# TailLightPrototypeRev3LEDs.net
KiCad netlist of a schematic drawn in Altium Designer
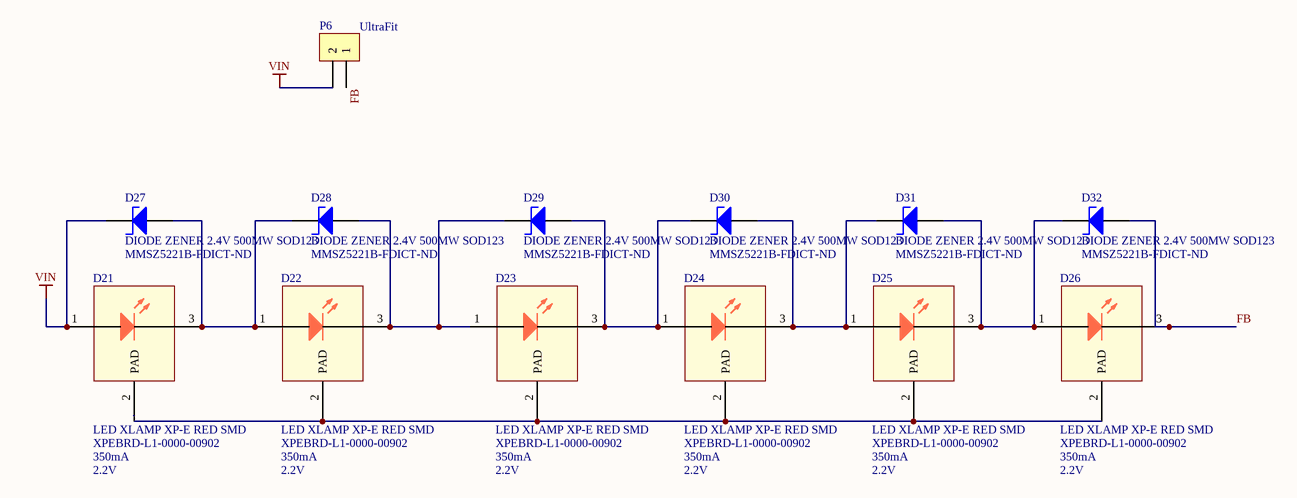
[diagram p0: TailLightPrototypeRev3LEDs.SchDoc]

(export (version "E")
  (design (tool "Eeschema 10.0.6"))
  (components
    (comp (ref "D21")
      (value "LED XLAMP XP-E RED SMD")
      (footprint "LED CREE XP-E2 1414 2-SMD")
      (description "LED Lighting Color XLamp® XP-E2 Red 623nm (620nm ~ 625nm) 1414 (3535 Metric)")
      (fields
        (field (name "MANUFACTURER") "Cree")
        (field (name "MANUFACTURER PART NUMBER") "XPEBRD-L1-0000-00902")
        (field (name "TEST CURRENT") "350mA")
        (field (name "FORWARD VOLTAGE") "2.2V")
      )
      (libsource (lib "Schematic Diagrams") (part "LED XLAMP XP-E RED SMD"))
    )
    (comp (ref "D22")
      (value "LED XLAMP XP-E RED SMD")
      (footprint "LED CREE XP-E2 1414 2-SMD")
      (description "LED Lighting Color XLamp® XP-E2 Red 623nm (620nm ~ 625nm) 1414 (3535 Metric)")
      (fields
        (field (name "MANUFACTURER") "Cree")
        (field (name "MANUFACTURER PART NUMBER") "XPEBRD-L1-0000-00902")
        (field (name "TEST CURRENT") "350mA")
        (field (name "FORWARD VOLTAGE") "2.2V")
      )
      (libsource (lib "Schematic Diagrams") (part "LED XLAMP XP-E RED SMD"))
    )
    (comp (ref "D23")
      (value "LED XLAMP XP-E RED SMD")
      (footprint "LED CREE XP-E2 1414 2-SMD")
      (description "LED Lighting Color XLamp® XP-E2 Red 623nm (620nm ~ 625nm) 1414 (3535 Metric)")
      (fields
        (field (name "MANUFACTURER") "Cree")
        (field (name "MANUFACTURER PART NUMBER") "XPEBRD-L1-0000-00902")
        (field (name "TEST CURRENT") "350mA")
        (field (name "FORWARD VOLTAGE") "2.2V")
      )
      (libsource (lib "Schematic Diagrams") (part "LED XLAMP XP-E RED SMD"))
    )
    (comp (ref "D24")
      (value "LED XLAMP XP-E RED SMD")
      (footprint "LED CREE XP-E2 1414 2-SMD")
      (description "LED Lighting Color XLamp® XP-E2 Red 623nm (620nm ~ 625nm) 1414 (3535 Metric)")
      (fields
        (field (name "MANUFACTURER") "Cree")
        (field (name "MANUFACTURER PART NUMBER") "XPEBRD-L1-0000-00902")
        (field (name "TEST CURRENT") "350mA")
        (field (name "FORWARD VOLTAGE") "2.2V")
      )
      (libsource (lib "Schematic Diagrams") (part "LED XLAMP XP-E RED SMD"))
    )
    (comp (ref "D25")
      (value "LED XLAMP XP-E RED SMD")
      (footprint "LED CREE XP-E2 1414 2-SMD")
      (description "LED Lighting Color XLamp® XP-E2 Red 623nm (620nm ~ 625nm) 1414 (3535 Metric)")
      (fields
        (field (name "MANUFACTURER") "Cree")
        (field (name "MANUFACTURER PART NUMBER") "XPEBRD-L1-0000-00902")
        (field (name "TEST CURRENT") "350mA")
        (field (name "FORWARD VOLTAGE") "2.2V")
      )
      (libsource (lib "Schematic Diagrams") (part "LED XLAMP XP-E RED SMD"))
    )
    (comp (ref "D26")
      (value "LED XLAMP XP-E RED SMD")
      (footprint "LED CREE XP-E2 1414 2-SMD")
      (description "LED Lighting Color XLamp® XP-E2 Red 623nm (620nm ~ 625nm) 1414 (3535 Metric)")
      (fields
        (field (name "MANUFACTURER") "Cree")
        (field (name "MANUFACTURER PART NUMBER") "XPEBRD-L1-0000-00902")
        (field (name "TEST CURRENT") "350mA")
        (field (name "FORWARD VOLTAGE") "2.2V")
      )
      (libsource (lib "Schematic Diagrams") (part "LED XLAMP XP-E RED SMD"))
    )
    (comp (ref "D27")
      (value "DIODE ZENER 2.4V 500MW SOD123")
      (footprint "DIODE SOD123")
      (description "Zener Diode 2.4V 500mW ±5% Surface Mount SOD-123")
      (fields (field (name "TOLERANCE") "5%") (field (name "SUPPLIER PART NUMBER 1") "MMSZ5221B-FDICT-ND"))
      (libsource (lib "Schematic Diagrams") (part "DIODE ZENER 2.4V 500MW SOD123"))
    )
    (comp (ref "D28")
      (value "DIODE ZENER 2.4V 500MW SOD123")
      (footprint "DIODE SOD123")
      (description "Zener Diode 2.4V 500mW ±5% Surface Mount SOD-123")
      (fields (field (name "TOLERANCE") "5%") (field (name "SUPPLIER PART NUMBER 1") "MMSZ5221B-FDICT-ND"))
      (libsource (lib "Schematic Diagrams") (part "DIODE ZENER 2.4V 500MW SOD123"))
    )
    (comp (ref "D29")
      (value "DIODE ZENER 2.4V 500MW SOD123")
      (footprint "DIODE SOD123")
      (description "Zener Diode 2.4V 500mW ±5% Surface Mount SOD-123")
      (fields (field (name "TOLERANCE") "5%") (field (name "SUPPLIER PART NUMBER 1") "MMSZ5221B-FDICT-ND"))
      (libsource (lib "Schematic Diagrams") (part "DIODE ZENER 2.4V 500MW SOD123"))
    )
    (comp (ref "D30")
      (value "DIODE ZENER 2.4V 500MW SOD123")
      (footprint "DIODE SOD123")
      (description "Zener Diode 2.4V 500mW ±5% Surface Mount SOD-123")
      (fields (field (name "TOLERANCE") "5%") (field (name "SUPPLIER PART NUMBER 1") "MMSZ5221B-FDICT-ND"))
      (libsource (lib "Schematic Diagrams") (part "DIODE ZENER 2.4V 500MW SOD123"))
    )
    (comp (ref "D31")
      (value "DIODE ZENER 2.4V 500MW SOD123")
      (footprint "DIODE SOD123")
      (description "Zener Diode 2.4V 500mW ±5% Surface Mount SOD-123")
      (fields (field (name "TOLERANCE") "5%") (field (name "SUPPLIER PART NUMBER 1") "MMSZ5221B-FDICT-ND"))
      (libsource (lib "Schematic Diagrams") (part "DIODE ZENER 2.4V 500MW SOD123"))
    )
    (comp (ref "D32")
      (value "DIODE ZENER 2.4V 500MW SOD123")
      (footprint "DIODE SOD123")
      (description "Zener Diode 2.4V 500mW ±5% Surface Mount SOD-123")
      (fields (field (name "TOLERANCE") "5%") (field (name "SUPPLIER PART NUMBER 1") "MMSZ5221B-FDICT-ND"))
      (libsource (lib "Schematic Diagrams") (part "DIODE ZENER 2.4V 500MW SOD123"))
    )
    (comp (ref "P6")
      (value "CONN 2POS ULTRA-FIT 0.138\"")
      (footprint "CONN, 2POS ULTRA-FIT")
      (description "2 Positions Header, Shrouded Connector 0.138\" (3.50mm) Through Hole Gold")
      (fields (field (name "VOLTAGE") "400V") (field (name "SERIES") "UltraFit"))
      (libsource (lib "Schematic Diagrams") (part "CONN 2POS ULTRA-FIT 0.138{dblquote}"))
    )
  )
  (nets
    (net (code "1") (name "/FB") (class "Default")
      (node (ref "D26") (pin "3") (pinfunction "K_3") (pintype "passive"))
      (node (ref "D32") (pin "2") (pinfunction "A_2") (pintype "passive"))
      (node (ref "P6") (pin "1") (pinfunction "1_1") (pintype "passive"))
    )
    (net (code "2") (name "Net-(D21-K)") (class "Default")
      (node (ref "D21") (pin "3") (pinfunction "K_3") (pintype "passive"))
      (node (ref "D22") (pin "1") (pinfunction "A_1") (pintype "passive"))
      (node (ref "D27") (pin "2") (pinfunction "A_2") (pintype "passive"))
      (node (ref "D28") (pin "1") (pinfunction "K_1") (pintype "passive"))
    )
    (net (code "3") (name "Net-(D21-PAD)") (class "Default")
      (node (ref "D21") (pin "2") (pinfunction "PAD_2") (pintype "passive"))
      (node (ref "D22") (pin "2") (pinfunction "PAD_2") (pintype "passive"))
      (node (ref "D23") (pin "2") (pinfunction "PAD_2") (pintype "passive"))
      (node (ref "D24") (pin "2") (pinfunction "PAD_2") (pintype "passive"))
      (node (ref "D25") (pin "2") (pinfunction "PAD_2") (pintype "passive"))
      (node (ref "D26") (pin "2") (pinfunction "PAD_2") (pintype "passive"))
    )
    (net (code "4") (name "Net-(D22-K)") (class "Default")
      (node (ref "D22") (pin "3") (pinfunction "K_3") (pintype "passive"))
      (node (ref "D23") (pin "1") (pinfunction "A_1") (pintype "passive"))
      (node (ref "D28") (pin "2") (pinfunction "A_2") (pintype "passive"))
      (node (ref "D29") (pin "1") (pinfunction "K_1") (pintype "passive"))
    )
    (net (code "5") (name "Net-(D23-K)") (class "Default")
      (node (ref "D23") (pin "3") (pinfunction "K_3") (pintype "passive"))
      (node (ref "D24") (pin "1") (pinfunction "A_1") (pintype "passive"))
      (node (ref "D29") (pin "2") (pinfunction "A_2") (pintype "passive"))
      (node (ref "D30") (pin "1") (pinfunction "K_1") (pintype "passive"))
    )
    (net (code "6") (name "Net-(D24-K)") (class "Default")
      (node (ref "D24") (pin "3") (pinfunction "K_3") (pintype "passive"))
      (node (ref "D25") (pin "1") (pinfunction "A_1") (pintype "passive"))
      (node (ref "D30") (pin "2") (pinfunction "A_2") (pintype "passive"))
      (node (ref "D31") (pin "1") (pinfunction "K_1") (pintype "passive"))
    )
    (net (code "7") (name "Net-(D25-K)") (class "Default")
      (node (ref "D25") (pin "3") (pinfunction "K_3") (pintype "passive"))
      (node (ref "D26") (pin "1") (pinfunction "A_1") (pintype "passive"))
      (node (ref "D31") (pin "2") (pinfunction "A_2") (pintype "passive"))
      (node (ref "D32") (pin "1") (pinfunction "K_1") (pintype "passive"))
    )
    (net (code "8") (name "VIN") (class "Default")
      (node (ref "D21") (pin "1") (pinfunction "A_1") (pintype "passive"))
      (node (ref "D27") (pin "1") (pinfunction "K_1") (pintype "passive"))
      (node (ref "P6") (pin "2") (pinfunction "2_2") (pintype "passive"))
    )
  )
)
